# controller.net
KiCad netlist of a schematic drawn in EAGLE
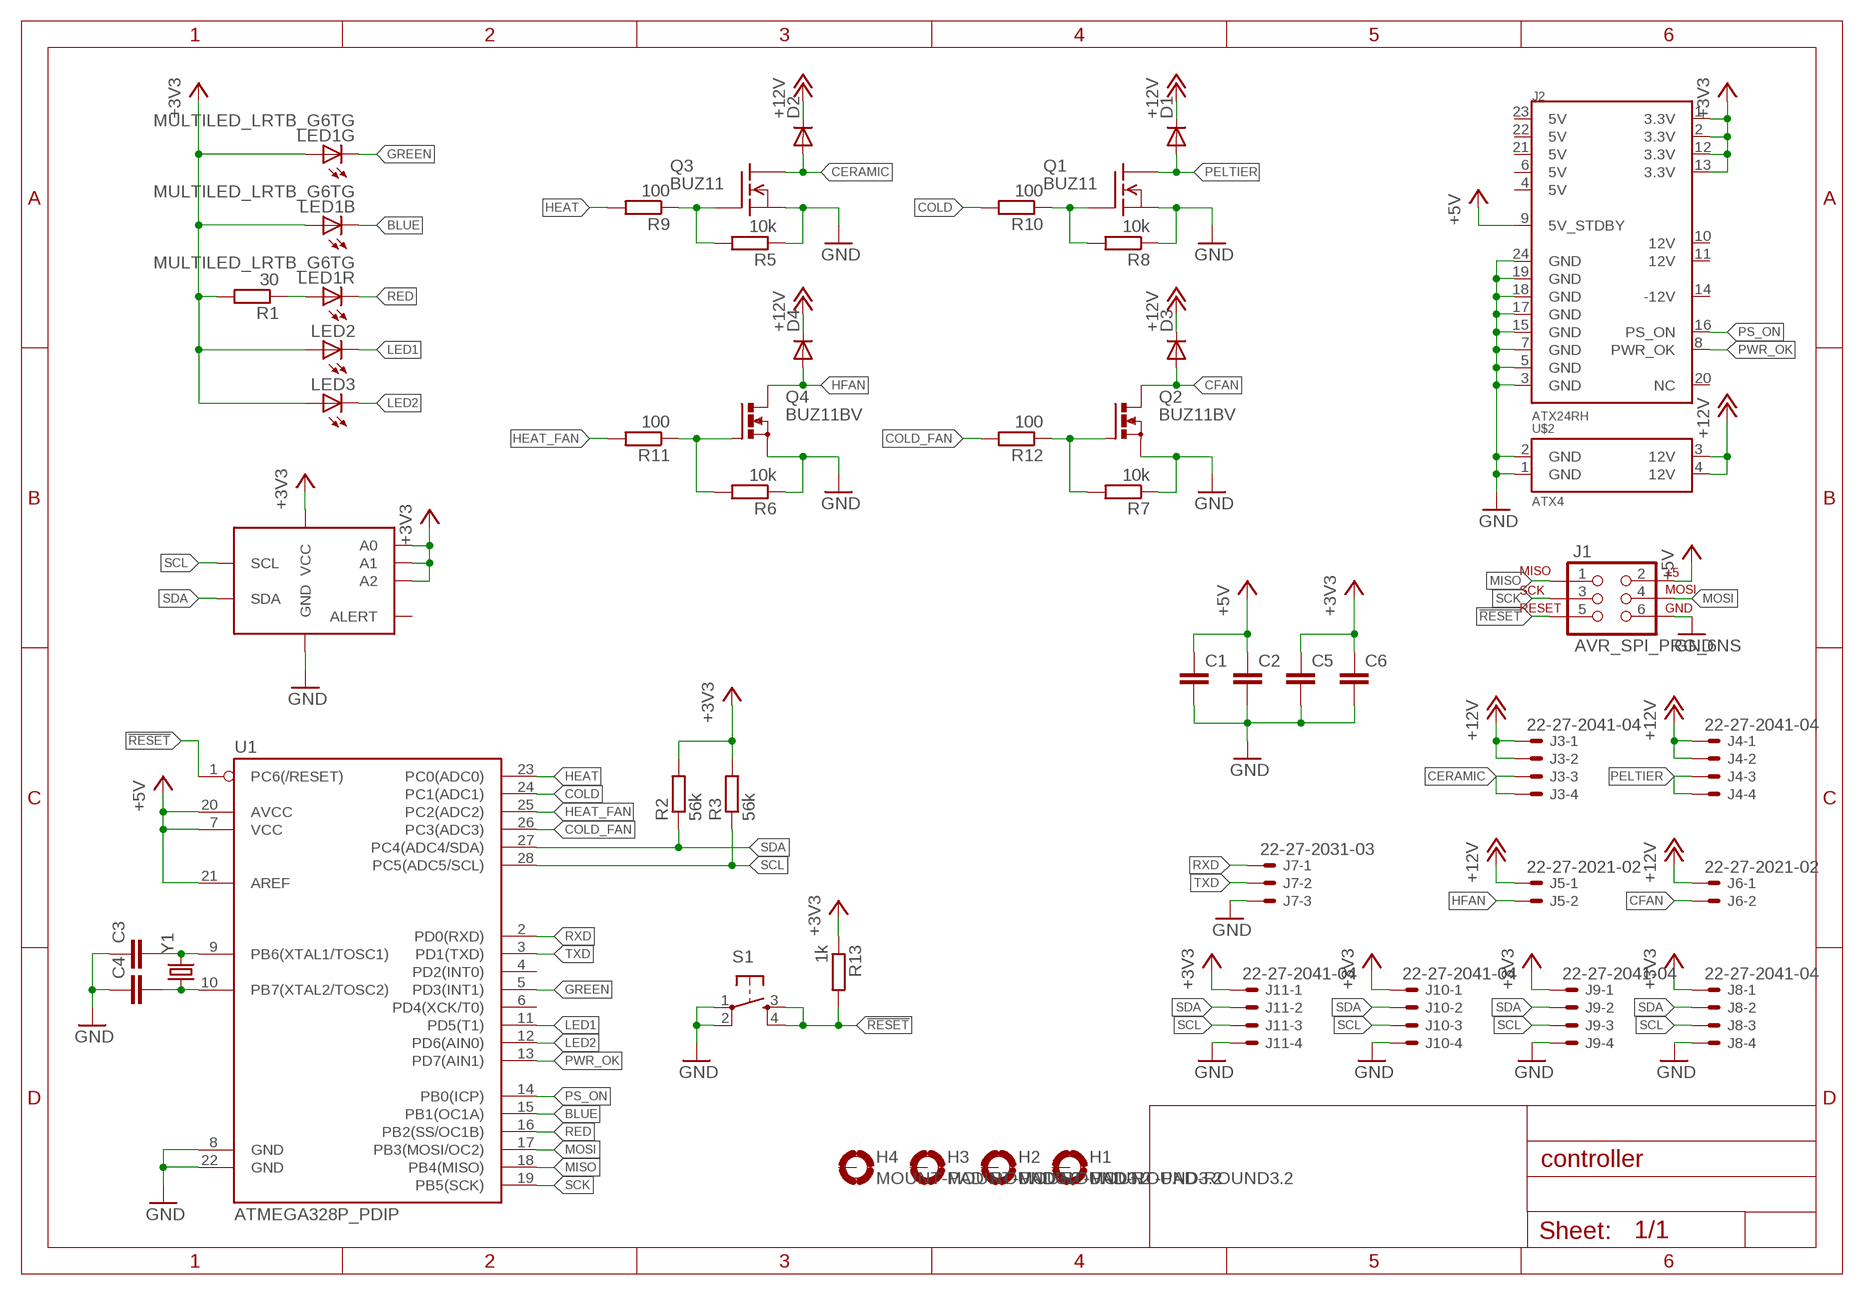
[diagram p0: schematic, sheet 1]

(export (version "E")
  (design (tool "Eeschema 10.0.6"))
  (components
    (comp (ref "C1")
      (value "C-EUC0603")
      (footprint "eagle-import:C0603")
      (libsource (lib "eagle-import") (part "C-EUC0603"))
    )
    (comp (ref "C2")
      (value "C-EUC0603")
      (footprint "eagle-import:C0603")
      (libsource (lib "eagle-import") (part "C-EUC0603"))
    )
    (comp (ref "C3")
      (value "C-EUC0603K")
      (footprint "eagle-import:C0603K")
      (libsource (lib "eagle-import") (part "C-EUC0603K"))
    )
    (comp (ref "C4")
      (value "C-EUC0603K")
      (footprint "eagle-import:C0603K")
      (libsource (lib "eagle-import") (part "C-EUC0603K"))
    )
    (comp (ref "C5")
      (value "C-EUC0603")
      (footprint "eagle-import:C0603")
      (libsource (lib "eagle-import") (part "C-EUC0603"))
    )
    (comp (ref "C6")
      (value "C-EUC0603")
      (footprint "eagle-import:C0603")
      (libsource (lib "eagle-import") (part "C-EUC0603"))
    )
    (comp (ref "D1")
      (value "DIODE-DO201-15")
      (footprint "eagle-import:DO201-15")
      (libsource (lib "eagle-import") (part "DIODE-DO201-15"))
    )
    (comp (ref "D2")
      (value "DIODE-DO201-15")
      (footprint "eagle-import:DO201-15")
      (libsource (lib "eagle-import") (part "DIODE-DO201-15"))
    )
    (comp (ref "D3")
      (value "DIODE-DO201-15")
      (footprint "eagle-import:DO201-15")
      (libsource (lib "eagle-import") (part "DIODE-DO201-15"))
    )
    (comp (ref "D4")
      (value "DIODE-DO201-15")
      (footprint "eagle-import:DO201-15")
      (libsource (lib "eagle-import") (part "DIODE-DO201-15"))
    )
    (comp (ref "H1")
      (value "MOUNT-PAD-ROUND3.2")
      (footprint "eagle-import:3,2-PAD")
      (libsource (lib "eagle-import") (part "MOUNT-PAD-ROUND3.2"))
    )
    (comp (ref "H2")
      (value "MOUNT-PAD-ROUND3.2")
      (footprint "eagle-import:3,2-PAD")
      (libsource (lib "eagle-import") (part "MOUNT-PAD-ROUND3.2"))
    )
    (comp (ref "H3")
      (value "MOUNT-PAD-ROUND3.2")
      (footprint "eagle-import:3,2-PAD")
      (libsource (lib "eagle-import") (part "MOUNT-PAD-ROUND3.2"))
    )
    (comp (ref "H4")
      (value "MOUNT-PAD-ROUND3.2")
      (footprint "eagle-import:3,2-PAD")
      (libsource (lib "eagle-import") (part "MOUNT-PAD-ROUND3.2"))
    )
    (comp (ref "J1")
      (value "AVR_SPI_PRG_6NS")
      (footprint "eagle-import:2X3-NS")
      (libsource (lib "eagle-import") (part "AVR_SPI_PRG_6NS"))
    )
    (comp (ref "J2")
      (value "ATX24RH")
      (footprint "eagle-import:ATX24_RIGHT_ANGLE")
      (libsource (lib "eagle-import") (part "ATX24RH"))
    )
    (comp (ref "J3")
      (value "22-27-2041-04")
      (footprint "eagle-import:6410-04")
      (libsource (lib "eagle-import") (part "22-?-0427-2041"))
    )
    (comp (ref "J4")
      (value "22-27-2041-04")
      (footprint "eagle-import:6410-04")
      (libsource (lib "eagle-import") (part "22-?-0427-2041"))
    )
    (comp (ref "J5")
      (value "22-27-2021-02")
      (footprint "eagle-import:6410-02")
      (libsource (lib "eagle-import") (part "22-?-0227-2021"))
    )
    (comp (ref "J6")
      (value "22-27-2021-02")
      (footprint "eagle-import:6410-02")
      (libsource (lib "eagle-import") (part "22-?-0227-2021"))
    )
    (comp (ref "J7")
      (value "22-27-2031-03")
      (footprint "eagle-import:6410-03")
      (libsource (lib "eagle-import") (part "22-?-0327-2031"))
    )
    (comp (ref "J8")
      (value "22-27-2041-04")
      (footprint "eagle-import:6410-04")
      (libsource (lib "eagle-import") (part "22-?-0427-2041"))
    )
    (comp (ref "J9")
      (value "22-27-2041-04")
      (footprint "eagle-import:6410-04")
      (libsource (lib "eagle-import") (part "22-?-0427-2041"))
    )
    (comp (ref "J10")
      (value "22-27-2041-04")
      (footprint "eagle-import:6410-04")
      (libsource (lib "eagle-import") (part "22-?-0427-2041"))
    )
    (comp (ref "J11")
      (value "22-27-2041-04")
      (footprint "eagle-import:6410-04")
      (libsource (lib "eagle-import") (part "22-?-0427-2041"))
    )
    (comp (ref "LED1")
      (value "MULTILED_LRTB_G6TG")
      (footprint "eagle-import:P-LCC-6_TOPLED")
      (libsource (lib "eagle-import") (part "MULTILED_LRTB_G6TG"))
    )
    (comp (ref "LED2")
      (value "LEDSML1206")
      (footprint "eagle-import:SML1206")
      (libsource (lib "eagle-import") (part "LEDSML1206"))
    )
    (comp (ref "LED3")
      (value "LEDSML1206")
      (footprint "eagle-import:SML1206")
      (libsource (lib "eagle-import") (part "LEDSML1206"))
    )
    (comp (ref "Q1")
      (value "BUZ11")
      (footprint "eagle-import:TO220")
      (libsource (lib "eagle-import") (part "BUZ11"))
    )
    (comp (ref "Q2")
      (value "BUZ11BV")
      (footprint "eagle-import:TO220BV")
      (libsource (lib "eagle-import") (part "BUZ11BV"))
    )
    (comp (ref "Q3")
      (value "BUZ11")
      (footprint "eagle-import:TO220")
      (libsource (lib "eagle-import") (part "BUZ11"))
    )
    (comp (ref "Q4")
      (value "BUZ11BV")
      (footprint "eagle-import:TO220BV")
      (libsource (lib "eagle-import") (part "BUZ11BV"))
    )
    (comp (ref "R1")
      (value "30")
      (footprint "eagle-import:R0603")
      (libsource (lib "eagle-import") (part "R-EU_R0603"))
    )
    (comp (ref "R2")
      (value "56k")
      (footprint "eagle-import:R0603")
      (libsource (lib "eagle-import") (part "R-EU_R0603"))
    )
    (comp (ref "R3")
      (value "56k")
      (footprint "eagle-import:R0603")
      (libsource (lib "eagle-import") (part "R-EU_R0603"))
    )
    (comp (ref "R5")
      (value "10k")
      (footprint "eagle-import:R0603")
      (libsource (lib "eagle-import") (part "R-EU_R0603"))
    )
    (comp (ref "R6")
      (value "10k")
      (footprint "eagle-import:R0603")
      (libsource (lib "eagle-import") (part "R-EU_R0603"))
    )
    (comp (ref "R7")
      (value "10k")
      (footprint "eagle-import:R0603")
      (libsource (lib "eagle-import") (part "R-EU_R0603"))
    )
    (comp (ref "R8")
      (value "10k")
      (footprint "eagle-import:R0603")
      (libsource (lib "eagle-import") (part "R-EU_R0603"))
    )
    (comp (ref "R9")
      (value "100")
      (footprint "eagle-import:R0603")
      (libsource (lib "eagle-import") (part "R-EU_R0603"))
    )
    (comp (ref "R10")
      (value "100")
      (footprint "eagle-import:R0603")
      (libsource (lib "eagle-import") (part "R-EU_R0603"))
    )
    (comp (ref "R11")
      (value "100")
      (footprint "eagle-import:R0603")
      (libsource (lib "eagle-import") (part "R-EU_R0603"))
    )
    (comp (ref "R12")
      (value "100")
      (footprint "eagle-import:R0603")
      (libsource (lib "eagle-import") (part "R-EU_R0603"))
    )
    (comp (ref "R13")
      (value "1k")
      (footprint "eagle-import:R0603")
      (libsource (lib "eagle-import") (part "R-EU_R0603"))
    )
    (comp (ref "S1")
      (value "TAC_SWITCHPTH")
      (footprint "eagle-import:TACTILE-PTH")
      (libsource (lib "eagle-import") (part "TAC_SWITCHPTH"))
    )
    (comp (ref "U$1")
      (value "TMP175")
      (footprint "eagle-import:MSOP8")
      (libsource (lib "eagle-import") (part "TMP175"))
    )
    (comp (ref "U$2")
      (value "ATX4")
      (footprint "eagle-import:ATX4")
      (libsource (lib "eagle-import") (part "ATX4"))
    )
    (comp (ref "U1")
      (value "ATMEGA328P_PDIP")
      (footprint "eagle-import:DIL28-3")
      (libsource (lib "eagle-import") (part "ATMEGA328P_PDIP"))
    )
    (comp (ref "Y1")
      (value "CRYSTALHC49UV")
      (footprint "eagle-import:HC49U-V")
      (libsource (lib "eagle-import") (part "CRYSTALHC49UV"))
    )
  )
  (nets
    (net (code "1") (name "+3V3") (class "Default")
      (node (ref "C5") (pin "1") (pinfunction "1_1") (pintype "passive"))
      (node (ref "C6") (pin "1") (pinfunction "1_1") (pintype "passive"))
      (node (ref "J10") (pin "1") (pinfunction "S_1") (pintype "passive"))
      (node (ref "J11") (pin "1") (pinfunction "S_1") (pintype "passive"))
      (node (ref "J2") (pin "1") (pinfunction "3.3V_1") (pintype "bidirectional"))
      (node (ref "J2") (pin "12") (pinfunction "3.3V_12") (pintype "bidirectional"))
      (node (ref "J2") (pin "13") (pinfunction "3.3V_13") (pintype "bidirectional"))
      (node (ref "J2") (pin "2") (pinfunction "3.3V_2") (pintype "bidirectional"))
      (node (ref "J8") (pin "1") (pinfunction "S_1") (pintype "passive"))
      (node (ref "J9") (pin "1") (pinfunction "S_1") (pintype "passive"))
      (node (ref "LED1") (pin "A2") (pinfunction "A_A2") (pintype "passive"))
      (node (ref "LED1") (pin "A3") (pinfunction "A_A3") (pintype "passive"))
      (node (ref "LED2") (pin "A") (pinfunction "A_A") (pintype "passive"))
      (node (ref "LED3") (pin "A") (pinfunction "A_A") (pintype "passive"))
      (node (ref "R1") (pin "2") (pinfunction "2_2") (pintype "passive"))
      (node (ref "R13") (pin "1") (pinfunction "1_1") (pintype "passive"))
      (node (ref "R2") (pin "2") (pinfunction "2_2") (pintype "passive"))
      (node (ref "R3") (pin "2") (pinfunction "2_2") (pintype "passive"))
      (node (ref "U$1") (pin "5") (pinfunction "A2_5") (pintype "bidirectional"))
      (node (ref "U$1") (pin "6") (pinfunction "A1_6") (pintype "bidirectional"))
      (node (ref "U$1") (pin "7") (pinfunction "A0_7") (pintype "bidirectional"))
      (node (ref "U$1") (pin "8") (pinfunction "VCC_8") (pintype "bidirectional"))
    )
    (net (code "2") (name "+5V") (class "Default")
      (node (ref "C1") (pin "1") (pinfunction "1_1") (pintype "passive"))
      (node (ref "C2") (pin "1") (pinfunction "1_1") (pintype "passive"))
      (node (ref "J1") (pin "2") (pinfunction "2_2") (pintype "passive"))
      (node (ref "J2") (pin "9") (pinfunction "5V_STDBY_9") (pintype "bidirectional"))
      (node (ref "U1") (pin "20") (pinfunction "AVCC_20") (pintype "bidirectional"))
      (node (ref "U1") (pin "21") (pinfunction "AREF_21") (pintype "bidirectional"))
      (node (ref "U1") (pin "7") (pinfunction "VCC_7") (pintype "bidirectional"))
    )
    (net (code "3") (name "+12V") (class "Default")
      (node (ref "D1") (pin "C") (pinfunction "C_C") (pintype "passive"))
      (node (ref "D2") (pin "C") (pinfunction "C_C") (pintype "passive"))
      (node (ref "D3") (pin "C") (pinfunction "C_C") (pintype "passive"))
      (node (ref "D4") (pin "C") (pinfunction "C_C") (pintype "passive"))
      (node (ref "J3") (pin "1") (pinfunction "S_1") (pintype "passive"))
      (node (ref "J3") (pin "2") (pinfunction "S_2") (pintype "passive"))
      (node (ref "J4") (pin "1") (pinfunction "S_1") (pintype "passive"))
      (node (ref "J4") (pin "2") (pinfunction "S_2") (pintype "passive"))
      (node (ref "J5") (pin "1") (pinfunction "S_1") (pintype "passive"))
      (node (ref "J6") (pin "1") (pinfunction "S_1") (pintype "passive"))
      (node (ref "U$2") (pin "3") (pinfunction "12V_3") (pintype "bidirectional"))
      (node (ref "U$2") (pin "4") (pinfunction "12V_4") (pintype "bidirectional"))
    )
    (net (code "4") (name "/~{RESET}") (class "Default")
      (node (ref "J1") (pin "5") (pinfunction "5_5") (pintype "passive"))
      (node (ref "R13") (pin "2") (pinfunction "2_2") (pintype "passive"))
      (node (ref "S1") (pin "3") (pinfunction "3_3") (pintype "passive"))
      (node (ref "S1") (pin "4") (pinfunction "4_4") (pintype "passive"))
      (node (ref "U1") (pin "1") (pinfunction "PC6(/RESET)_1") (pintype "bidirectional"))
    )
    (net (code "5") (name "BLUE") (class "Default")
      (node (ref "LED1") (pin "C3") (pinfunction "C_C3") (pintype "passive"))
      (node (ref "U1") (pin "15") (pinfunction "PB1(OC1A)_15") (pintype "bidirectional"))
    )
    (net (code "6") (name "CERAMIC") (class "Default")
      (node (ref "D2") (pin "A") (pinfunction "A_A") (pintype "passive"))
      (node (ref "J3") (pin "3") (pinfunction "S_3") (pintype "passive"))
      (node (ref "J3") (pin "4") (pinfunction "S_4") (pintype "passive"))
      (node (ref "Q3") (pin "2") (pinfunction "D_2") (pintype "passive"))
    )
    (net (code "7") (name "CFAN") (class "Default")
      (node (ref "D3") (pin "A") (pinfunction "A_A") (pintype "passive"))
      (node (ref "J6") (pin "2") (pinfunction "S_2") (pintype "passive"))
      (node (ref "Q2") (pin "D") (pinfunction "D_D") (pintype "passive"))
    )
    (net (code "8") (name "COLD") (class "Default")
      (node (ref "R10") (pin "2") (pinfunction "2_2") (pintype "passive"))
      (node (ref "U1") (pin "24") (pinfunction "PC1(ADC1)_24") (pintype "bidirectional"))
    )
    (net (code "9") (name "COLD_FAN") (class "Default")
      (node (ref "R12") (pin "2") (pinfunction "2_2") (pintype "passive"))
      (node (ref "U1") (pin "26") (pinfunction "PC3(ADC3)_26") (pintype "bidirectional"))
    )
    (net (code "10") (name "GND") (class "Default")
      (node (ref "C1") (pin "2") (pinfunction "2_2") (pintype "passive"))
      (node (ref "C2") (pin "2") (pinfunction "2_2") (pintype "passive"))
      (node (ref "C3") (pin "1") (pinfunction "1_1") (pintype "passive"))
      (node (ref "C4") (pin "1") (pinfunction "1_1") (pintype "passive"))
      (node (ref "C5") (pin "2") (pinfunction "2_2") (pintype "passive"))
      (node (ref "C6") (pin "2") (pinfunction "2_2") (pintype "passive"))
      (node (ref "J1") (pin "6") (pinfunction "6_6") (pintype "passive"))
      (node (ref "J10") (pin "4") (pinfunction "S_4") (pintype "passive"))
      (node (ref "J11") (pin "4") (pinfunction "S_4") (pintype "passive"))
      (node (ref "J2") (pin "15") (pinfunction "GND_15") (pintype "bidirectional"))
      (node (ref "J2") (pin "17") (pinfunction "GND_17") (pintype "bidirectional"))
      (node (ref "J2") (pin "18") (pinfunction "GND_18") (pintype "bidirectional"))
      (node (ref "J2") (pin "19") (pinfunction "GND_19") (pintype "bidirectional"))
      (node (ref "J2") (pin "24") (pinfunction "GND_24") (pintype "bidirectional"))
      (node (ref "J2") (pin "3") (pinfunction "GND_3") (pintype "bidirectional"))
      (node (ref "J2") (pin "5") (pinfunction "GND_5") (pintype "bidirectional"))
      (node (ref "J2") (pin "7") (pinfunction "GND_7") (pintype "bidirectional"))
      (node (ref "J7") (pin "3") (pinfunction "S_3") (pintype "passive"))
      (node (ref "J8") (pin "4") (pinfunction "S_4") (pintype "passive"))
      (node (ref "J9") (pin "4") (pinfunction "S_4") (pintype "passive"))
      (node (ref "Q1") (pin "3") (pinfunction "S_3") (pintype "passive"))
      (node (ref "Q2") (pin "S") (pinfunction "S_S") (pintype "passive"))
      (node (ref "Q3") (pin "3") (pinfunction "S_3") (pintype "passive"))
      (node (ref "Q4") (pin "S") (pinfunction "S_S") (pintype "passive"))
      (node (ref "R5") (pin "1") (pinfunction "1_1") (pintype "passive"))
      (node (ref "R6") (pin "1") (pinfunction "1_1") (pintype "passive"))
      (node (ref "R7") (pin "1") (pinfunction "1_1") (pintype "passive"))
      (node (ref "R8") (pin "1") (pinfunction "1_1") (pintype "passive"))
      (node (ref "S1") (pin "1") (pinfunction "1_1") (pintype "passive"))
      (node (ref "S1") (pin "2") (pinfunction "2_2") (pintype "passive"))
      (node (ref "U$1") (pin "4") (pinfunction "GND_4") (pintype "bidirectional"))
      (node (ref "U$2") (pin "1") (pinfunction "GND_1") (pintype "bidirectional"))
      (node (ref "U$2") (pin "2") (pinfunction "GND_2") (pintype "bidirectional"))
      (node (ref "U1") (pin "22") (pinfunction "GND_22") (pintype "bidirectional"))
      (node (ref "U1") (pin "8") (pinfunction "GND_8") (pintype "bidirectional"))
    )
    (net (code "11") (name "GREEN") (class "Default")
      (node (ref "LED1") (pin "C2") (pinfunction "C_C2") (pintype "passive"))
      (node (ref "U1") (pin "5") (pinfunction "PD3(INT1)_5") (pintype "bidirectional"))
    )
    (net (code "12") (name "HEAT") (class "Default")
      (node (ref "R9") (pin "2") (pinfunction "2_2") (pintype "passive"))
      (node (ref "U1") (pin "23") (pinfunction "PC0(ADC0)_23") (pintype "bidirectional"))
    )
    (net (code "13") (name "HEAT_FAN") (class "Default")
      (node (ref "R11") (pin "2") (pinfunction "2_2") (pintype "passive"))
      (node (ref "U1") (pin "25") (pinfunction "PC2(ADC2)_25") (pintype "bidirectional"))
    )
    (net (code "14") (name "HFAN") (class "Default")
      (node (ref "D4") (pin "A") (pinfunction "A_A") (pintype "passive"))
      (node (ref "J5") (pin "2") (pinfunction "S_2") (pintype "passive"))
      (node (ref "Q4") (pin "D") (pinfunction "D_D") (pintype "passive"))
    )
    (net (code "15") (name "LED1") (class "Default")
      (node (ref "LED2") (pin "C") (pinfunction "C_C") (pintype "passive"))
      (node (ref "U1") (pin "11") (pinfunction "PD5(T1)_11") (pintype "bidirectional"))
    )
    (net (code "16") (name "LED2") (class "Default")
      (node (ref "LED3") (pin "C") (pinfunction "C_C") (pintype "passive"))
      (node (ref "U1") (pin "12") (pinfunction "PD6(AIN0)_12") (pintype "bidirectional"))
    )
    (net (code "17") (name "MISO") (class "Default")
      (node (ref "J1") (pin "1") (pinfunction "1_1") (pintype "passive"))
      (node (ref "U1") (pin "18") (pinfunction "PB4(MISO)_18") (pintype "bidirectional"))
    )
    (net (code "18") (name "MOSI") (class "Default")
      (node (ref "J1") (pin "4") (pinfunction "4_4") (pintype "passive"))
      (node (ref "U1") (pin "17") (pinfunction "PB3(MOSI/OC2)_17") (pintype "bidirectional"))
    )
    (net (code "19") (name "Net-(LED1C-A)") (class "Default")
      (node (ref "LED1") (pin "A1") (pinfunction "A_A1") (pintype "passive"))
      (node (ref "R1") (pin "1") (pinfunction "1_1") (pintype "passive"))
    )
    (net (code "20") (name "Net-(Q1-G)") (class "Default")
      (node (ref "Q1") (pin "1") (pinfunction "G_1") (pintype "passive"))
      (node (ref "R10") (pin "1") (pinfunction "1_1") (pintype "passive"))
      (node (ref "R8") (pin "2") (pinfunction "2_2") (pintype "passive"))
    )
    (net (code "21") (name "Net-(Q2-PadG)") (class "Default")
      (node (ref "Q2") (pin "G") (pinfunction "G_G") (pintype "passive"))
      (node (ref "R12") (pin "1") (pinfunction "1_1") (pintype "passive"))
      (node (ref "R7") (pin "2") (pinfunction "2_2") (pintype "passive"))
    )
    (net (code "22") (name "Net-(Q3-G)") (class "Default")
      (node (ref "Q3") (pin "1") (pinfunction "G_1") (pintype "passive"))
      (node (ref "R5") (pin "2") (pinfunction "2_2") (pintype "passive"))
      (node (ref "R9") (pin "1") (pinfunction "1_1") (pintype "passive"))
    )
    (net (code "23") (name "Net-(Q4-PadG)") (class "Default")
      (node (ref "Q4") (pin "G") (pinfunction "G_G") (pintype "passive"))
      (node (ref "R11") (pin "1") (pinfunction "1_1") (pintype "passive"))
      (node (ref "R6") (pin "2") (pinfunction "2_2") (pintype "passive"))
    )
    (net (code "24") (name "Net-(U1-PB6(XTAL1{slash}TOSC1))") (class "Default")
      (node (ref "C3") (pin "2") (pinfunction "2_2") (pintype "passive"))
      (node (ref "U1") (pin "9") (pinfunction "PB6(XTAL1/TOSC1)_9") (pintype "bidirectional"))
      (node (ref "Y1") (pin "2") (pinfunction "2_2") (pintype "passive"))
    )
    (net (code "25") (name "Net-(U1-PB7(XTAL2{slash}TOSC2))") (class "Default")
      (node (ref "C4") (pin "2") (pinfunction "2_2") (pintype "passive"))
      (node (ref "U1") (pin "10") (pinfunction "PB7(XTAL2/TOSC2)_10") (pintype "bidirectional"))
      (node (ref "Y1") (pin "1") (pinfunction "1_1") (pintype "passive"))
    )
    (net (code "26") (name "PELTIER") (class "Default")
      (node (ref "D1") (pin "A") (pinfunction "A_A") (pintype "passive"))
      (node (ref "J4") (pin "3") (pinfunction "S_3") (pintype "passive"))
      (node (ref "J4") (pin "4") (pinfunction "S_4") (pintype "passive"))
      (node (ref "Q1") (pin "2") (pinfunction "D_2") (pintype "passive"))
    )
    (net (code "27") (name "PS_ON") (class "Default")
      (node (ref "J2") (pin "16") (pinfunction "PS_ON_16") (pintype "bidirectional"))
      (node (ref "U1") (pin "14") (pinfunction "PB0(ICP)_14") (pintype "bidirectional"))
    )
    (net (code "28") (name "PWR_OK") (class "Default")
      (node (ref "J2") (pin "8") (pinfunction "PWR_OK_8") (pintype "bidirectional"))
      (node (ref "U1") (pin "13") (pinfunction "PD7(AIN1)_13") (pintype "bidirectional"))
    )
    (net (code "29") (name "RED") (class "Default")
      (node (ref "LED1") (pin "C1") (pinfunction "C_C1") (pintype "passive"))
      (node (ref "U1") (pin "16") (pinfunction "PB2(SS/OC1B)_16") (pintype "bidirectional"))
    )
    (net (code "30") (name "RXD") (class "Default")
      (node (ref "J7") (pin "1") (pinfunction "S_1") (pintype "passive"))
      (node (ref "U1") (pin "2") (pinfunction "PD0(RXD)_2") (pintype "bidirectional"))
    )
    (net (code "31") (name "SCK") (class "Default")
      (node (ref "J1") (pin "3") (pinfunction "3_3") (pintype "passive"))
      (node (ref "U1") (pin "19") (pinfunction "PB5(SCK)_19") (pintype "bidirectional"))
    )
    (net (code "32") (name "SCL") (class "Default")
      (node (ref "J10") (pin "3") (pinfunction "S_3") (pintype "passive"))
      (node (ref "J11") (pin "3") (pinfunction "S_3") (pintype "passive"))
      (node (ref "J8") (pin "3") (pinfunction "S_3") (pintype "passive"))
      (node (ref "J9") (pin "3") (pinfunction "S_3") (pintype "passive"))
      (node (ref "R3") (pin "1") (pinfunction "1_1") (pintype "passive"))
      (node (ref "U$1") (pin "2") (pinfunction "SCL_2") (pintype "bidirectional"))
      (node (ref "U1") (pin "28") (pinfunction "PC5(ADC5/SCL)_28") (pintype "bidirectional"))
    )
    (net (code "33") (name "SDA") (class "Default")
      (node (ref "J10") (pin "2") (pinfunction "S_2") (pintype "passive"))
      (node (ref "J11") (pin "2") (pinfunction "S_2") (pintype "passive"))
      (node (ref "J8") (pin "2") (pinfunction "S_2") (pintype "passive"))
      (node (ref "J9") (pin "2") (pinfunction "S_2") (pintype "passive"))
      (node (ref "R2") (pin "1") (pinfunction "1_1") (pintype "passive"))
      (node (ref "U$1") (pin "1") (pinfunction "SDA_1") (pintype "bidirectional"))
      (node (ref "U1") (pin "27") (pinfunction "PC4(ADC4/SDA)_27") (pintype "bidirectional"))
    )
    (net (code "34") (name "TXD") (class "Default")
      (node (ref "J7") (pin "2") (pinfunction "S_2") (pintype "passive"))
      (node (ref "U1") (pin "3") (pinfunction "PD1(TXD)_3") (pintype "bidirectional"))
    )
    (net (code "35") (name "unconnected-(H1-MOUNT-PadB3,2)") (class "Default")
      (node (ref "H1") (pin "B3,2") (pinfunction "MOUNT_B3,2") (pintype "passive"))
    )
    (net (code "36") (name "unconnected-(H2-MOUNT-PadB3,2)") (class "Default")
      (node (ref "H2") (pin "B3,2") (pinfunction "MOUNT_B3,2") (pintype "passive"))
    )
    (net (code "37") (name "unconnected-(H3-MOUNT-PadB3,2)") (class "Default")
      (node (ref "H3") (pin "B3,2") (pinfunction "MOUNT_B3,2") (pintype "passive"))
    )
    (net (code "38") (name "unconnected-(H4-MOUNT-PadB3,2)") (class "Default")
      (node (ref "H4") (pin "B3,2") (pinfunction "MOUNT_B3,2") (pintype "passive"))
    )
    (net (code "39") (name "unconnected-(J2--12V-Pad14)") (class "Default")
      (node (ref "J2") (pin "14") (pinfunction "-12V_14") (pintype "bidirectional"))
    )
    (net (code "40") (name "unconnected-(J2-5V-Pad4)") (class "Default")
      (node (ref "J2") (pin "4") (pinfunction "5V_4") (pintype "bidirectional"))
    )
    (net (code "41") (name "unconnected-(J2-5V-Pad6)") (class "Default")
      (node (ref "J2") (pin "6") (pinfunction "5V_6") (pintype "bidirectional"))
    )
    (net (code "42") (name "unconnected-(J2-5V-Pad21)") (class "Default")
      (node (ref "J2") (pin "21") (pinfunction "5V_21") (pintype "bidirectional"))
    )
    (net (code "43") (name "unconnected-(J2-5V-Pad22)") (class "Default")
      (node (ref "J2") (pin "22") (pinfunction "5V_22") (pintype "bidirectional"))
    )
    (net (code "44") (name "unconnected-(J2-5V-Pad23)") (class "Default")
      (node (ref "J2") (pin "23") (pinfunction "5V_23") (pintype "bidirectional"))
    )
    (net (code "45") (name "unconnected-(J2-12V-Pad10)") (class "Default")
      (node (ref "J2") (pin "10") (pinfunction "12V_10") (pintype "bidirectional"))
    )
    (net (code "46") (name "unconnected-(J2-12V-Pad11)") (class "Default")
      (node (ref "J2") (pin "11") (pinfunction "12V_11") (pintype "bidirectional"))
    )
    (net (code "47") (name "unconnected-(J2-NC-Pad20)") (class "Default")
      (node (ref "J2") (pin "20") (pinfunction "NC_20") (pintype "bidirectional"))
    )
    (net (code "48") (name "unconnected-(U$1-ALERT-Pad3)") (class "Default")
      (node (ref "U$1") (pin "3") (pinfunction "ALERT_3") (pintype "bidirectional"))
    )
    (net (code "49") (name "unconnected-(U1-PD2(INT0)-Pad4)") (class "Default")
      (node (ref "U1") (pin "4") (pinfunction "PD2(INT0)_4") (pintype "bidirectional"))
    )
    (net (code "50") (name "unconnected-(U1-PD4(XCK{slash}T0)-Pad6)") (class "Default")
      (node (ref "U1") (pin "6") (pinfunction "PD4(XCK/T0)_6") (pintype "bidirectional"))
    )
  )
)
